# MAIN.net
KiCad netlist of a schematic drawn in Altium Designer
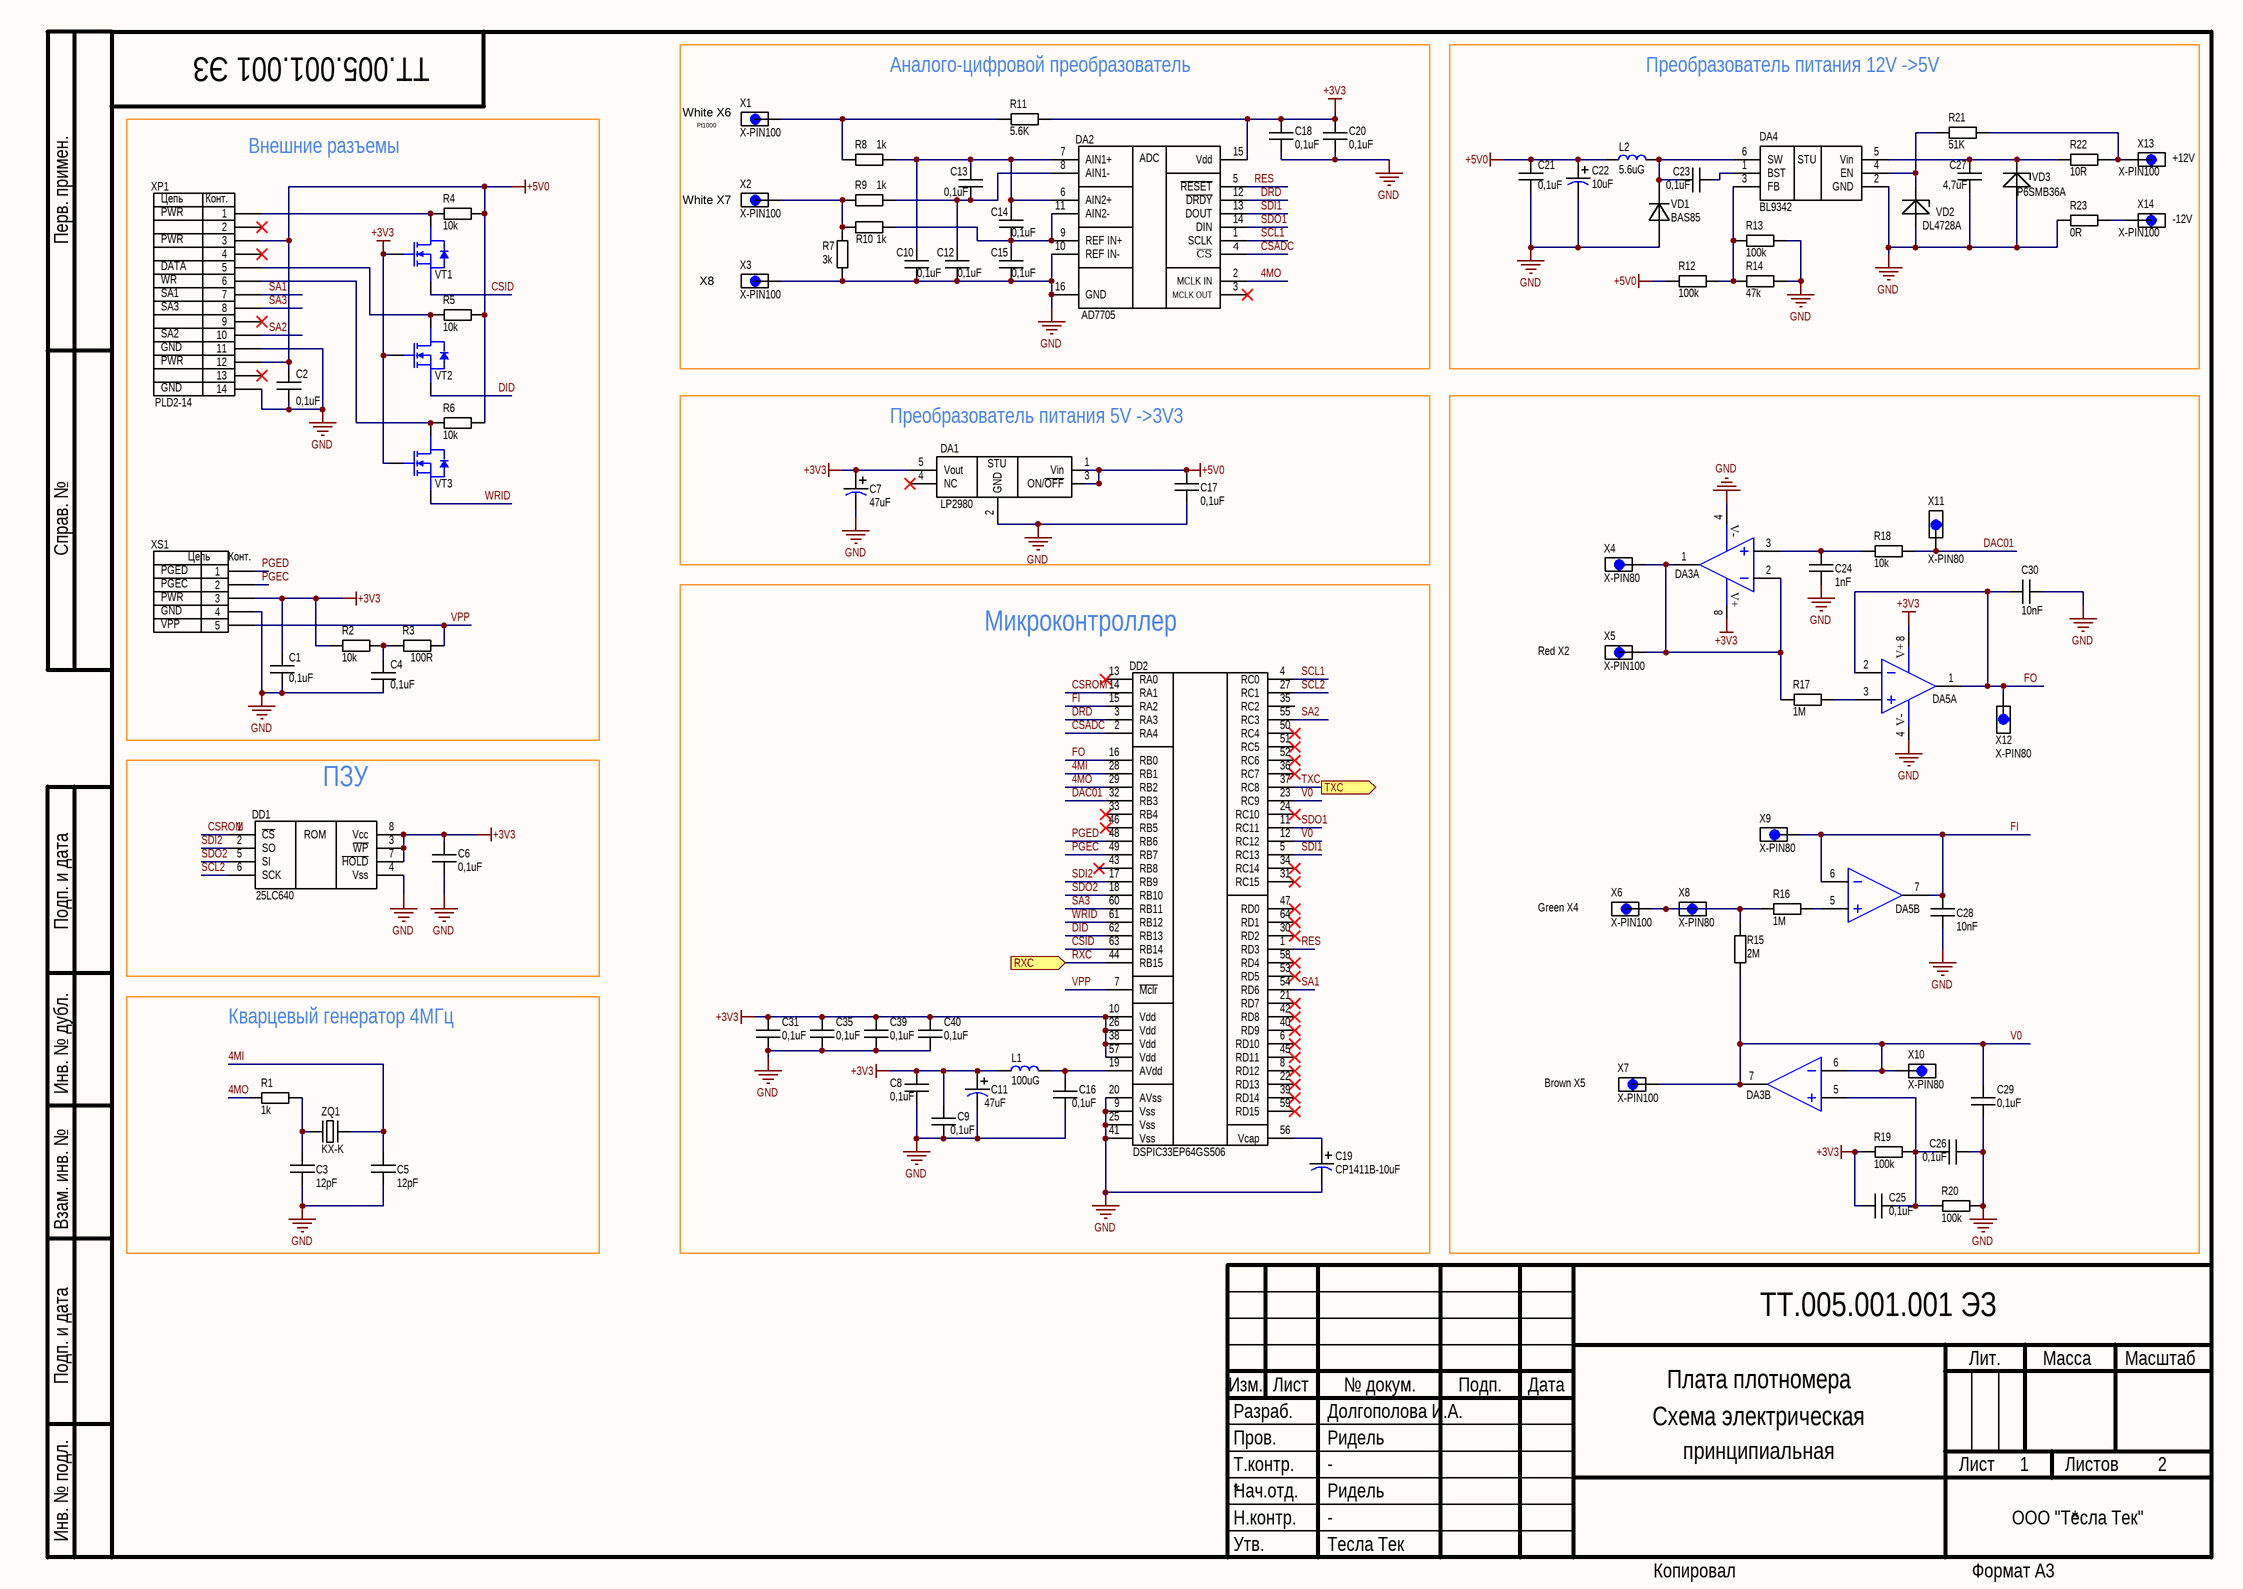
[diagram p0: MAIN.SCHDOC]

(export (version "E")
  (design (tool "Eeschema 10.0.6"))
  (components
    (comp (ref "C1")
      (value "0,1uF")
      (footprint "0805C")
      (description "C0805 0,1uF")
      (fields
        (field (name "PART NUMBER") "SMD CAP CER 0.1uF ±10% 25V X7R 0805")
        (field (name "ADDED_BY") "ridel_av@teslatec.ru")
      )
      (libsource (lib "81801_1") (part "C0805-0,1uF"))
    )
    (comp (ref "C2")
      (value "0,1uF")
      (footprint "0805C")
      (description "C0805 0,1uF")
      (fields
        (field (name "PART NUMBER") "SMD CAP CER 0.1uF ±10% 25V X7R 0805")
        (field (name "ADDED_BY") "ridel_av@teslatec.ru")
      )
      (libsource (lib "81801_1") (part "C0805-0,1uF"))
    )
    (comp (ref "C3")
      (value "12pF")
      (footprint "0805C")
      (description "C0805 12pF")
      (fields
        (field (name "PART NUMBER") "SMD CAP CER 12pF ±10% 10V X7R 0805")
        (field (name "ADDED_BY") "ridel_av@teslatec.ru")
      )
      (libsource (lib "81801_1") (part "C0805-12pF"))
    )
    (comp (ref "C4")
      (value "0,1uF")
      (footprint "0805C")
      (description "C0805 0,1uF")
      (fields
        (field (name "PART NUMBER") "SMD CAP CER 0.1uF ±10% 25V X7R 0805")
        (field (name "ADDED_BY") "ridel_av@teslatec.ru")
      )
      (libsource (lib "81801_1") (part "C0805-0,1uF"))
    )
    (comp (ref "C5")
      (value "12pF")
      (footprint "0805C")
      (description "C0805 12pF")
      (fields
        (field (name "PART NUMBER") "SMD CAP CER 12pF ±10% 10V X7R 0805")
        (field (name "ADDED_BY") "ridel_av@teslatec.ru")
      )
      (libsource (lib "81801_1") (part "C0805-12pF"))
    )
    (comp (ref "C6")
      (value "0,1uF")
      (footprint "0805C")
      (description "C0805 0,1uF")
      (fields
        (field (name "PART NUMBER") "SMD CAP CER 0.1uF ±10% 25V X7R 0805")
        (field (name "ADDED_BY") "ridel_av@teslatec.ru")
      )
      (libsource (lib "81801_1") (part "C0805-0,1uF"))
    )
    (comp (ref "C7")
      (value "47uF")
      (footprint "B1411_3528")
      (description "CP1411B 47UF 6V3")
      (fields
        (field (name "PART NUMBER") "SMD CAP TANTAL 47uF ±10% 6V3 1411B")
        (field (name "ADDED_BY") "ridel_av@teslatec.ru")
      )
      (libsource (lib "81801_1") (part "CP1411B-47UF"))
    )
    (comp (ref "C8")
      (value "0,1uF")
      (footprint "0805C")
      (description "C0805 0,1uF")
      (fields
        (field (name "PART NUMBER") "SMD CAP CER 0.1uF ±10% 25V X7R 0805")
        (field (name "ADDED_BY") "ridel_av@teslatec.ru")
      )
      (libsource (lib "81801_1") (part "C0805-0,1uF"))
    )
    (comp (ref "C9")
      (value "0,1uF")
      (footprint "0805C")
      (description "C0805 0,1uF")
      (fields
        (field (name "PART NUMBER") "SMD CAP CER 0.1uF ±10% 25V X7R 0805")
        (field (name "ADDED_BY") "ridel_av@teslatec.ru")
      )
      (libsource (lib "81801_1") (part "C0805-0,1uF"))
    )
    (comp (ref "C10")
      (value "0,1uF")
      (footprint "0805C")
      (description "C0805 0,1uF")
      (fields
        (field (name "PART NUMBER") "SMD CAP CER 0.1uF ±10% 25V X7R 0805")
        (field (name "ADDED_BY") "ridel_av@teslatec.ru")
      )
      (libsource (lib "81801_1") (part "C0805-0,1uF"))
    )
    (comp (ref "C11")
      (value "47uF")
      (footprint "B1411_3528")
      (description "CP1411B 47UF 6V3")
      (fields
        (field (name "PART NUMBER") "SMD CAP TANTAL 47uF ±10% 6V3 1411B")
        (field (name "ADDED_BY") "ridel_av@teslatec.ru")
      )
      (libsource (lib "81801_1") (part "CP1411B-47UF"))
    )
    (comp (ref "C12")
      (value "0,1uF")
      (footprint "0805C")
      (description "C0805 0,1uF")
      (fields
        (field (name "PART NUMBER") "SMD CAP CER 0.1uF ±10% 25V X7R 0805")
        (field (name "ADDED_BY") "ridel_av@teslatec.ru")
      )
      (libsource (lib "81801_1") (part "C0805-0,1uF"))
    )
    (comp (ref "C13")
      (value "0,1uF")
      (footprint "0805C")
      (description "C0805 0,1uF")
      (fields
        (field (name "PART NUMBER") "SMD CAP CER 0.1uF ±10% 25V X7R 0805")
        (field (name "ADDED_BY") "ridel_av@teslatec.ru")
      )
      (libsource (lib "81801_1") (part "C0805-0,1uF"))
    )
    (comp (ref "C14")
      (value "0,1uF")
      (footprint "0805C")
      (description "C0805 0,1uF")
      (fields
        (field (name "PART NUMBER") "SMD CAP CER 0.1uF ±10% 25V X7R 0805")
        (field (name "ADDED_BY") "ridel_av@teslatec.ru")
      )
      (libsource (lib "81801_1") (part "C0805-0,1uF"))
    )
    (comp (ref "C15")
      (value "0,1uF")
      (footprint "0805C")
      (description "C0805 0,1uF")
      (fields
        (field (name "PART NUMBER") "SMD CAP CER 0.1uF ±10% 25V X7R 0805")
        (field (name "ADDED_BY") "ridel_av@teslatec.ru")
      )
      (libsource (lib "81801_1") (part "C0805-0,1uF"))
    )
    (comp (ref "C16")
      (value "0,1uF")
      (footprint "0805C")
      (description "C0805 0,1uF")
      (fields
        (field (name "PART NUMBER") "SMD CAP CER 0.1uF ±10% 25V X7R 0805")
        (field (name "ADDED_BY") "ridel_av@teslatec.ru")
      )
      (libsource (lib "81801_1") (part "C0805-0,1uF"))
    )
    (comp (ref "C17")
      (value "0,1uF")
      (footprint "0805C")
      (description "C0805 0,1uF")
      (fields
        (field (name "PART NUMBER") "SMD CAP CER 0.1uF ±10% 25V X7R 0805")
        (field (name "ADDED_BY") "ridel_av@teslatec.ru")
      )
      (libsource (lib "81801_1") (part "C0805-0,1uF"))
    )
    (comp (ref "C18")
      (value "0,1uF")
      (footprint "0805C")
      (description "C0805 0,1uF")
      (fields
        (field (name "PART NUMBER") "SMD CAP CER 0.1uF ±10% 25V X7R 0805")
        (field (name "ADDED_BY") "ridel_av@teslatec.ru")
      )
      (libsource (lib "81801_1") (part "C0805-0,1uF"))
    )
    (comp (ref "C19")
      (value "CP1411B-10uF")
      (footprint "B1411_3528")
      (description "CP1411B 10uF 6V3")
      (fields
        (field (name "PART NUMBER") "SMD CAP TANTAL 10uF ±10% 6V3 1411B")
        (field (name "ADDED_BY") "ridel_av@teslatec.ru")
      )
      (libsource (lib "81801_1") (part "CP1411B-10uF"))
    )
    (comp (ref "C20")
      (value "0,1uF")
      (footprint "0805C")
      (description "C0805 0,1uF")
      (fields
        (field (name "PART NUMBER") "SMD CAP CER 0.1uF ±10% 25V X7R 0805")
        (field (name "ADDED_BY") "ridel_av@teslatec.ru")
      )
      (libsource (lib "81801_1") (part "C0805-0,1uF"))
    )
    (comp (ref "C21")
      (value "0,1uF")
      (footprint "0805C")
      (description "C0805 0,1uF")
      (fields
        (field (name "PART NUMBER") "SMD CAP CER 0.1uF ±10% 25V X7R 0805")
        (field (name "ADDED_BY") "ridel_av@teslatec.ru")
      )
      (libsource (lib "81801_1") (part "C0805-0,1uF"))
    )
    (comp (ref "C22")
      (value "10uF")
      (footprint "B1411_3528")
      (description "CP1411B 10uF 10V")
      (fields
        (field (name "PART NUMBER") "SMD CAP TANTAL 10uF ±10% 10V 1411B")
        (field (name "ADDED_BY") "ridel_av@teslatec.ru")
      )
      (libsource (lib "81801_1") (part "CP1411B-10uF-10V"))
    )
    (comp (ref "C23")
      (value "0,1uF")
      (footprint "0805C")
      (description "C0805 0,1uF")
      (fields
        (field (name "PART NUMBER") "SMD CAP CER 0.1uF ±10% 25V X7R 0805")
        (field (name "ADDED_BY") "ridel_av@teslatec.ru")
      )
      (libsource (lib "81801_1") (part "C0805-0,1uF"))
    )
    (comp (ref "C24")
      (value "1nF")
      (footprint "0805C")
      (description "C0805 1nF")
      (fields
        (field (name "PART NUMBER") "SMD CAP CER 1nF ±10% 50V X7R 0805")
        (field (name "ADDED_BY") "ridel_av@teslatec.ru")
      )
      (libsource (lib "81801_1") (part "C0805-1nF"))
    )
    (comp (ref "C25")
      (value "0,1uF")
      (footprint "0805C")
      (description "C0805 0,1uF")
      (fields
        (field (name "PART NUMBER") "SMD CAP CER 0.1uF ±10% 25V X7R 0805")
        (field (name "ADDED_BY") "ridel_av@teslatec.ru")
      )
      (libsource (lib "81801_1") (part "C0805-0,1uF"))
    )
    (comp (ref "C26")
      (value "0,1uF")
      (footprint "0805C")
      (description "C0805 0,1uF")
      (fields
        (field (name "PART NUMBER") "SMD CAP CER 0.1uF ±10% 25V X7R 0805")
        (field (name "ADDED_BY") "ridel_av@teslatec.ru")
      )
      (libsource (lib "81801_1") (part "C0805-0,1uF"))
    )
    (comp (ref "C27")
      (value "4,7uF")
      (footprint "0805C")
      (description "C0805 4,7uF 50V")
      (fields
        (field (name "PART NUMBER") "SMD CAP CER 4.7uF ±10% 50V X7R 0805")
        (field (name "ADDED_BY") "ridel_av@teslatec.ru")
      )
      (libsource (lib "81801_1") (part "C0805-4,7uF"))
    )
    (comp (ref "C28")
      (value "10nF")
      (footprint "0805C")
      (description "C0805 10nF")
      (fields
        (field (name "PART NUMBER") "SMD CAP CER 10nF ±10% 50V X7R 0805")
        (field (name "ADDED_BY") "ridel_av@teslatec.ru")
      )
      (libsource (lib "81801_1") (part "C0805-10nF"))
    )
    (comp (ref "C29")
      (value "0,1uF")
      (footprint "0805C")
      (description "C0805 0,1uF")
      (fields
        (field (name "PART NUMBER") "SMD CAP CER 0.1uF ±10% 25V X7R 0805")
        (field (name "ADDED_BY") "ridel_av@teslatec.ru")
      )
      (libsource (lib "81801_1") (part "C0805-0,1uF"))
    )
    (comp (ref "C30")
      (value "10nF")
      (footprint "0805C")
      (description "C0805 10nF")
      (fields
        (field (name "PART NUMBER") "SMD CAP CER 10nF ±10% 50V X7R 0805")
        (field (name "ADDED_BY") "ridel_av@teslatec.ru")
      )
      (libsource (lib "81801_1") (part "C0805-10nF"))
    )
    (comp (ref "C31")
      (value "0,1uF")
      (footprint "0805C")
      (description "C0805 0,1uF")
      (fields
        (field (name "PART NUMBER") "SMD CAP CER 0.1uF ±10% 25V X7R 0805")
        (field (name "ADDED_BY") "ridel_av@teslatec.ru")
      )
      (libsource (lib "81801_1") (part "C0805-0,1uF"))
    )
    (comp (ref "C35")
      (value "0,1uF")
      (footprint "0805C")
      (description "C0805 0,1uF")
      (fields
        (field (name "PART NUMBER") "SMD CAP CER 0.1uF ±10% 25V X7R 0805")
        (field (name "ADDED_BY") "ridel_av@teslatec.ru")
      )
      (libsource (lib "81801_1") (part "C0805-0,1uF"))
    )
    (comp (ref "C39")
      (value "0,1uF")
      (footprint "0805C")
      (description "C0805 0,1uF")
      (fields
        (field (name "PART NUMBER") "SMD CAP CER 0.1uF ±10% 25V X7R 0805")
        (field (name "ADDED_BY") "ridel_av@teslatec.ru")
      )
      (libsource (lib "81801_1") (part "C0805-0,1uF"))
    )
    (comp (ref "C40")
      (value "0,1uF")
      (footprint "0805C")
      (description "C0805 0,1uF")
      (fields
        (field (name "PART NUMBER") "SMD CAP CER 0.1uF ±10% 25V X7R 0805")
        (field (name "ADDED_BY") "ridel_av@teslatec.ru")
      )
      (libsource (lib "81801_1") (part "C0805-0,1uF"))
    )
    (comp (ref "DA1")
      (value "LP2980")
      (footprint "SOT23-5")
      (description "DA-STU-LP2980, 3.3V, 50mA")
      (fields
        (field (name "PART NUMBER") "LP2980IM5X-3.3/NOPB")
        (field (name "ADDED_BY") "ridel_av@teslatec.ru")
      )
      (libsource (lib "81801_1") (part "DA-STU-LP2980"))
    )
    (comp (ref "DA2")
      (value "AD7705")
      (footprint "SOIC-16")
      (description "DA-ADC-AD7705")
      (fields (field (name "PART NUMBER") "AD7705BR") (field (name "ADDED_BY") "ridel_av@teslatec.ru"))
      (libsource (lib "81801_1") (part "DA-ADC-AD7705SO"))
    )
    (comp (ref "DA3")
      (value "TP6002-SR")
      (footprint "SOIC-8")
      (description "100 mA Output Single-Supply Amplifier")
      (fields (field (name "ADDED_BY") "ridel_av@teslatec.ru"))
      (libsource (lib "81801_1") (part "TP6002-SR"))
    )
    (comp (ref "DA4")
      (value "BL9342")
      (footprint "SOT23-6")
      (description "STU-BL9342, 40V, 600mA")
      (fields (field (name "ADDED_BY") "ridel_av@teslatec.ru"))
      (libsource (lib "81801_1") (part "BL9342"))
    )
    (comp (ref "DA5")
      (value "TP6002-SR")
      (footprint "SOIC-8")
      (description "100 mA Output Single-Supply Amplifier")
      (fields (field (name "ADDED_BY") "ridel_av@teslatec.ru"))
      (libsource (lib "81801_1") (part "TP6002-SR"))
    )
    (comp (ref "DD1")
      (value "25LC640")
      (footprint "SOIC-8")
      (description "25LC640-E/SN, EEPROM, 64Kbit, 2MHz, SPI")
      (fields (field (name "PART NUMBER") "25LC640-E/SN") (field (name "ADDED_BY") "ridel_av@teslatec.ru"))
      (libsource (lib "81801_1") (part "25LC640"))
    )
    (comp (ref "DD2")
      (value "DSPIC33EP64GS506")
      (footprint "TQFP-64")
      (description "DD-CPU-DSPIC33EP64GS506")
      (fields (field (name "ADDED_BY") "ridel_av@teslatec.ru"))
      (libsource (lib "81801_1") (part "DD-CPU-DSPIC33EPXXGS506"))
    )
    (comp (ref "L1")
      (value "100uG")
      (footprint "L1206")
      (description "LQH31CN101K03L, 100 uG, 1206, 10%")
      (fields (field (name "PART NUMBER") "LQH31CN101K03L") (field (name "ADDED_BY") "ridel_av@teslatec.ru"))
      (libsource (lib "81801_1") (part "L1206-100uG"))
    )
    (comp (ref "L2")
      (value "5.6uG")
      (footprint "L1210")
      (description "LQH32MN5R6K23L, 5.6uG, 1210, 10%")
      (fields (field (name "PART NUMBER") "LQH32MN5R6K23L") (field (name "ADDED_BY") "ridel_av@teslatec.ru"))
      (libsource (lib "81801_1") (part "L1210-5.6uG"))
    )
    (comp (ref "R1")
      (value "1k")
      (footprint "R1206")
      (description "R1206 SMD 1k OHM 1% ±100ppm/°C")
      (fields
        (field (name "PART NUMBER") "SMD RES 1k OHM 1% ±100ppm/°C 1206")
        (field (name "ADDED_BY") "ridel_av@teslatec.ru")
      )
      (libsource (lib "81801_1") (part "R1206-1k"))
    )
    (comp (ref "R2")
      (value "10k")
      (footprint "R0805")
      (description "R0805 SMD 10k OHM 1% ±100ppm/°C")
      (fields
        (field (name "PART NUMBER") "SMD RES 10k OHM 1% ±100ppm/°C 0805")
        (field (name "ADDED_BY") "ridel_av@teslatec.ru")
      )
      (libsource (lib "81801_1") (part "R0805-10k"))
    )
    (comp (ref "R3")
      (value "100R")
      (footprint "R1206")
      (description "R1206 100 OHM 1% ±100ppm/°C")
      (fields
        (field (name "PART NUMBER") "SMD RES 100 OHM 1% ±100ppm/°C 1206")
        (field (name "ADDED_BY") "ridel_av@teslatec.ru")
      )
      (libsource (lib "81801_1") (part "R1206-100R"))
    )
    (comp (ref "R4")
      (value "10k")
      (footprint "R0805")
      (description "R0805 SMD 10k OHM 1% ±100ppm/°C")
      (fields
        (field (name "PART NUMBER") "SMD RES 10k OHM 1% ±100ppm/°C 0805")
        (field (name "ADDED_BY") "ridel_av@teslatec.ru")
      )
      (libsource (lib "81801_1") (part "R0805-10k"))
    )
    (comp (ref "R5")
      (value "10k")
      (footprint "R0805")
      (description "R0805 SMD 10k OHM 1% ±100ppm/°C")
      (fields
        (field (name "PART NUMBER") "SMD RES 10k OHM 1% ±100ppm/°C 0805")
        (field (name "ADDED_BY") "ridel_av@teslatec.ru")
      )
      (libsource (lib "81801_1") (part "R0805-10k"))
    )
    (comp (ref "R6")
      (value "10k")
      (footprint "R0805")
      (description "R0805 SMD 10k OHM 1% ±100ppm/°C")
      (fields
        (field (name "PART NUMBER") "SMD RES 10k OHM 1% ±100ppm/°C 0805")
        (field (name "ADDED_BY") "ridel_av@teslatec.ru")
      )
      (libsource (lib "81801_1") (part "R0805-10k"))
    )
    (comp (ref "R7")
      (value "3k")
      (footprint "R1206")
      (description "R1206 SMD 3k OHM 1% ±100ppm/°C")
      (fields
        (field (name "PART NUMBER") "SMD RES 1k OHM 1% ±100ppm/°C 1206")
        (field (name "ADDED_BY") "ridel_av@teslatec.ru")
      )
      (libsource (lib "81801_1") (part "R1206-3k"))
    )
    (comp (ref "R8")
      (value "1k")
      (footprint "R1206")
      (description "R1206 SMD 1k OHM 1% ±100ppm/°C")
      (fields
        (field (name "PART NUMBER") "SMD RES 1k OHM 1% ±100ppm/°C 1206")
        (field (name "ADDED_BY") "ridel_av@teslatec.ru")
      )
      (libsource (lib "81801_1") (part "R1206-1k"))
    )
    (comp (ref "R9")
      (value "1k")
      (footprint "R1206")
      (description "R1206 SMD 1k OHM 1% ±100ppm/°C")
      (fields
        (field (name "PART NUMBER") "SMD RES 1k OHM 1% ±100ppm/°C 1206")
        (field (name "ADDED_BY") "ridel_av@teslatec.ru")
      )
      (libsource (lib "81801_1") (part "R1206-1k"))
    )
    (comp (ref "R10")
      (value "1k")
      (footprint "R1206")
      (description "R1206 SMD 1k OHM 1% ±100ppm/°C")
      (fields
        (field (name "PART NUMBER") "SMD RES 1k OHM 1% ±100ppm/°C 1206")
        (field (name "ADDED_BY") "ridel_av@teslatec.ru")
      )
      (libsource (lib "81801_1") (part "R1206-1k"))
    )
    (comp (ref "R11")
      (value "5.6K")
      (footprint "R1206")
      (description "R1206 5.6k OHM 1% ±100ppm/°C")
      (fields
        (field (name "PART NUMBER") "SMD RES 5.6k OHM 1% ±100ppm/°C 1206")
        (field (name "ADDED_BY") "ridel_av@teslatec.ru")
      )
      (libsource (lib "81801_1") (part "R1206-5.6K"))
    )
    (comp (ref "R12")
      (value "100k")
      (footprint "R1206")
      (description "R1206 100k OHM 1% ±100ppm/°C")
      (fields
        (field (name "PART NUMBER") "SMD RES 100k OHM 1% ±100ppm/°C 1206")
        (field (name "ADDED_BY") "ridel_av@teslatec.ru")
      )
      (libsource (lib "81801_1") (part "R1206-100k"))
    )
    (comp (ref "R13")
      (value "100k")
      (footprint "R1206")
      (description "R1206 100k OHM 1% ±100ppm/°C")
      (fields
        (field (name "PART NUMBER") "SMD RES 100k OHM 1% ±100ppm/°C 1206")
        (field (name "ADDED_BY") "ridel_av@teslatec.ru")
      )
      (libsource (lib "81801_1") (part "R1206-100k"))
    )
    (comp (ref "R14")
      (value "47k")
      (footprint "R1206")
      (description "R1206 47k OHM 1% ±100ppm/°C")
      (fields
        (field (name "PART NUMBER") "SMD RES 47k OHM 1% ±100ppm/°C 1206")
        (field (name "ADDED_BY") "ridel_av@teslatec.ru")
      )
      (libsource (lib "81801_1") (part "R1206-47k"))
    )
    (comp (ref "R15")
      (value "2M")
      (footprint "R1206")
      (description "R1206 2M OHM 1% ±100ppm/°C")
      (fields
        (field (name "PART NUMBER") "SMD RES 2M OHM 1% ±100ppm/°C 1206")
        (field (name "ADDED_BY") "ridel_av@teslatec.ru")
      )
      (libsource (lib "81801_1") (part "R1206-2M"))
    )
    (comp (ref "R16")
      (value "1M")
      (footprint "R1206")
      (description "R1206 1M OHM 1% ±100ppm/°C")
      (fields
        (field (name "PART NUMBER") "SMD RES 1M OHM 1% ±100ppm/°C 1206")
        (field (name "ADDED_BY") "ridel_av@teslatec.ru")
      )
      (libsource (lib "81801_1") (part "R1206-1M"))
    )
    (comp (ref "R17")
      (value "1M")
      (footprint "R1206")
      (description "R1206 1M OHM 1% ±100ppm/°C")
      (fields
        (field (name "PART NUMBER") "SMD RES 1M OHM 1% ±100ppm/°C 1206")
        (field (name "ADDED_BY") "ridel_av@teslatec.ru")
      )
      (libsource (lib "81801_1") (part "R1206-1M"))
    )
    (comp (ref "R18")
      (value "10k")
      (footprint "R0805")
      (description "R0805 SMD 10k OHM 1% ±100ppm/°C")
      (fields
        (field (name "PART NUMBER") "SMD RES 10k OHM 1% ±100ppm/°C 0805")
        (field (name "ADDED_BY") "ridel_av@teslatec.ru")
      )
      (libsource (lib "81801_1") (part "R0805-10k"))
    )
    (comp (ref "R19")
      (value "100k")
      (footprint "R1206")
      (description "R1206 100k OHM 1% ±100ppm/°C")
      (fields
        (field (name "PART NUMBER") "SMD RES 100k OHM 1% ±100ppm/°C 1206")
        (field (name "ADDED_BY") "ridel_av@teslatec.ru")
      )
      (libsource (lib "81801_1") (part "R1206-100k"))
    )
    (comp (ref "R20")
      (value "100k")
      (footprint "R1206")
      (description "R1206 100k OHM 1% ±100ppm/°C")
      (fields
        (field (name "PART NUMBER") "SMD RES 100k OHM 1% ±100ppm/°C 1206")
        (field (name "ADDED_BY") "ridel_av@teslatec.ru")
      )
      (libsource (lib "81801_1") (part "R1206-100k"))
    )
    (comp (ref "R21")
      (value "51K")
      (footprint "R1206")
      (description "R1206 51K OHM 1% ±100ppm/°C")
      (fields
        (field (name "PART NUMBER") "SMD RES 51K OHM 1% ±100ppm/°C 1206")
        (field (name "ADDED_BY") "ridel_av@teslatec.ru")
      )
      (libsource (lib "81801_1") (part "R1206-51K"))
    )
    (comp (ref "R22")
      (value "10R")
      (footprint "R1206")
      (description "R1206 10 OHM 1% ±100ppm/°C")
      (fields
        (field (name "PART NUMBER") "SMD RES 10 OHM 1% ±100ppm/°C 1206")
        (field (name "ADDED_BY") "ridel_av@teslatec.ru")
      )
      (libsource (lib "81801_1") (part "R1206-10R"))
    )
    (comp (ref "R23")
      (value "0R")
      (footprint "R1206")
      (description "R1206-0R")
      (fields
        (field (name "PART NUMBER") "SMD RES 0 OHM 1% ±100ppm/°C 1206")
        (field (name "ADDED_BY") "ridel_av@teslatec.ru")
      )
      (libsource (lib "81801_1") (part "R1206-0R"))
    )
    (comp (ref "VD1")
      (value "BAS85")
      (footprint "SOD-80 MiniMELF")
      (description "BAS85 30В 0.2А")
      (fields (field (name "ADDED_BY") "ridel_av@teslatec.ru"))
      (libsource (lib "81801_1") (part "BAS85"))
    )
    (comp (ref "VD2")
      (value "DL4728A")
      (footprint "DO-213AB")
      (description "DL4728A, 3V3")
      (fields (field (name "ADDED_BY") "ridel_av@teslatec.ru"))
      (libsource (lib "81801_1") (part "DL4728A"))
    )
    (comp (ref "VD3")
      (value "P6SMB36A")
      (footprint "SMB(DO-214AA )")
      (description "P6SMB36A, 49.9V")
      (fields (field (name "ADDED_BY") "ridel_av@teslatec.ru"))
      (libsource (lib "81801_1") (part "P6SMB36A"))
    )
    (comp (ref "VT1")
      (value "VT-MOSFET-N-SOT23")
      (footprint "SOT-23-3")
      (description "2N7002, MOSFET-N, 60V, 115mA, SOT-23-3")
      (fields (field (name "PART NUMBER") "2N7002") (field (name "ADDED_BY") "ridel_av@teslatec.ru"))
      (libsource (lib "81801_1") (part "2N7002"))
    )
    (comp (ref "VT2")
      (value "VT-MOSFET-N-SOT23")
      (footprint "SOT-23-3")
      (description "2N7002, MOSFET-N, 60V, 115mA, SOT-23-3")
      (fields (field (name "PART NUMBER") "2N7002") (field (name "ADDED_BY") "ridel_av@teslatec.ru"))
      (libsource (lib "81801_1") (part "2N7002"))
    )
    (comp (ref "VT3")
      (value "VT-MOSFET-N-SOT23")
      (footprint "SOT-23-3")
      (description "2N7002, MOSFET-N, 60V, 115mA, SOT-23-3")
      (fields (field (name "PART NUMBER") "2N7002") (field (name "ADDED_BY") "ridel_av@teslatec.ru"))
      (libsource (lib "81801_1") (part "2N7002"))
    )
    (comp (ref "X1")
      (value "X-PIN100")
      (footprint "Xpin100")
      (fields (field (name "ADDED_BY") "ridel_av@teslatec.ru"))
      (libsource (lib "81801_1") (part "X-PIN100"))
    )
    (comp (ref "X2")
      (value "X-PIN100")
      (footprint "Xpin100")
      (fields (field (name "ADDED_BY") "ridel_av@teslatec.ru"))
      (libsource (lib "81801_1") (part "X-PIN100"))
    )
    (comp (ref "X3")
      (value "X-PIN100")
      (footprint "Xpin100")
      (fields (field (name "ADDED_BY") "ridel_av@teslatec.ru"))
      (libsource (lib "81801_1") (part "X-PIN100"))
    )
    (comp (ref "X4")
      (value "X-PIN80")
      (footprint "Xpin80")
      (fields (field (name "ADDED_BY") "ridel_av@teslatec.ru"))
      (libsource (lib "81801_1") (part "X-PIN80"))
    )
    (comp (ref "X5")
      (value "X-PIN100")
      (footprint "Xpin100")
      (fields (field (name "ADDED_BY") "ridel_av@teslatec.ru"))
      (libsource (lib "81801_1") (part "X-PIN100"))
    )
    (comp (ref "X6")
      (value "X-PIN100")
      (footprint "Xpin100")
      (fields (field (name "ADDED_BY") "ridel_av@teslatec.ru"))
      (libsource (lib "81801_1") (part "X-PIN100"))
    )
    (comp (ref "X7")
      (value "X-PIN100")
      (footprint "Xpin100")
      (fields (field (name "ADDED_BY") "ridel_av@teslatec.ru"))
      (libsource (lib "81801_1") (part "X-PIN100"))
    )
    (comp (ref "X8")
      (value "X-PIN80")
      (footprint "Xpin80")
      (fields (field (name "ADDED_BY") "ridel_av@teslatec.ru"))
      (libsource (lib "81801_1") (part "X-PIN80"))
    )
    (comp (ref "X9")
      (value "X-PIN80")
      (footprint "Xpin80")
      (fields (field (name "ADDED_BY") "ridel_av@teslatec.ru"))
      (libsource (lib "81801_1") (part "X-PIN80"))
    )
    (comp (ref "X10")
      (value "X-PIN80")
      (footprint "Xpin80")
      (fields (field (name "ADDED_BY") "ridel_av@teslatec.ru"))
      (libsource (lib "81801_1") (part "X-PIN80"))
    )
    (comp (ref "X11")
      (value "X-PIN80")
      (footprint "Xpin80")
      (fields (field (name "ADDED_BY") "ridel_av@teslatec.ru"))
      (libsource (lib "81801_1") (part "X-PIN80"))
    )
    (comp (ref "X12")
      (value "X-PIN80")
      (footprint "Xpin80")
      (fields (field (name "ADDED_BY") "ridel_av@teslatec.ru"))
      (libsource (lib "81801_1") (part "X-PIN80"))
    )
    (comp (ref "X13")
      (value "X-PIN100")
      (footprint "Xpin100")
      (fields (field (name "ADDED_BY") "ridel_av@teslatec.ru"))
      (libsource (lib "81801_1") (part "X-PIN100"))
    )
    (comp (ref "X14")
      (value "X-PIN100")
      (footprint "Xpin100")
      (fields (field (name "ADDED_BY") "ridel_av@teslatec.ru"))
      (libsource (lib "81801_1") (part "X-PIN100"))
    )
    (comp (ref "XP1")
      (value "PLD2-14")
      (footprint "PLD-14- 2.0mm")
      (fields
        (field (name "PART NUMBER") "DS1025-05-2X7P8BV1-B")
        (field (name "ADDED_BY") "ridel_av@teslatec.ru")
      )
      (libsource (lib "81801_1") (part "PLD2-14"))
    )
    (comp (ref "XS1")
      (value "PBS2-5")
      (footprint "PBS-5")
      (fields (field (name "PART NUMBER") "C6801-05ASGL00R") (field (name "ADDED_BY") "ridel_av@teslatec.ru"))
      (libsource (lib "81801_1") (part "PBS2-5"))
    )
    (comp (ref "ZQ1")
      (value "KX-K")
      (footprint "HC¦49US")
      (description "KX-K 4MHz HC/49US")
      (fields
        (field (name "PART NUMBER") "ABLS-4.000MHZ-K4T")
        (field (name "ADDED_BY") "ridel_av@teslatec.ru")
      )
      (libsource (lib "81801_1") (part "ABLS-4.000MHZ-K4T"))
    )
  )
  (nets
    (net (code "1") (name "+3V3") (class "Default")
      (node (ref "C1") (pin "1") (pinfunction "1_1") (pintype "passive"))
      (node (ref "C11") (pin "1") (pinfunction "1_1") (pintype "passive"))
      (node (ref "C18") (pin "2") (pinfunction "2_2") (pintype "passive"))
      (node (ref "C20") (pin "1") (pinfunction "1_1") (pintype "passive"))
      (node (ref "C25") (pin "1") (pinfunction "1_1") (pintype "passive"))
      (node (ref "C31") (pin "1") (pinfunction "1_1") (pintype "passive"))
      (node (ref "C35") (pin "1") (pinfunction "1_1") (pintype "passive"))
      (node (ref "C39") (pin "1") (pinfunction "1_1") (pintype "passive"))
      (node (ref "C40") (pin "1") (pinfunction "1_1") (pintype "passive"))
      (node (ref "C6") (pin "2") (pinfunction "2_2") (pintype "passive"))
      (node (ref "C7") (pin "1") (pinfunction "1_1") (pintype "passive"))
      (node (ref "C8") (pin "1") (pinfunction "1_1") (pintype "passive"))
      (node (ref "C9") (pin "1") (pinfunction "1_1") (pintype "passive"))
      (node (ref "DA1") (pin "5") (pinfunction "Vout_5") (pintype "passive"))
      (node (ref "DA2") (pin "15") (pinfunction "Vdd_15") (pintype "power_in"))
      (node (ref "DA3") (pin "8") (pinfunction "8_8") (pintype "passive"))
      (node (ref "DA5") (pin "8") (pinfunction "8_8") (pintype "passive"))
      (node (ref "DD1") (pin "3") (pinfunction "~{WP}_3") (pintype "passive"))
      (node (ref "DD1") (pin "7") (pinfunction "~{HOLD}_7") (pintype "passive"))
      (node (ref "DD1") (pin "8") (pinfunction "Vcc_8") (pintype "passive"))
      (node (ref "DD2") (pin "10") (pinfunction "Vdd_10") (pintype "passive"))
      (node (ref "DD2") (pin "26") (pinfunction "Vdd_26") (pintype "passive"))
      (node (ref "DD2") (pin "38") (pinfunction "Vdd_38") (pintype "passive"))
      (node (ref "DD2") (pin "57") (pinfunction "Vdd_57") (pintype "passive"))
      (node (ref "L1") (pin "1") (pinfunction "1_1") (pintype "passive"))
      (node (ref "R11") (pin "2") (pinfunction "2_2") (pintype "passive"))
      (node (ref "R19") (pin "1") (pinfunction "1_1") (pintype "passive"))
      (node (ref "R2") (pin "1") (pinfunction "1_1") (pintype "passive"))
      (node (ref "VT1") (pin "1") (pinfunction "1_1") (pintype "passive"))
      (node (ref "VT2") (pin "1") (pinfunction "1_1") (pintype "passive"))
      (node (ref "VT3") (pin "1") (pinfunction "1_1") (pintype "passive"))
      (node (ref "XS1") (pin "3") (pinfunction "3_3") (pintype "passive"))
    )
    (net (code "2") (name "+5V0") (class "Default")
      (node (ref "C17") (pin "1") (pinfunction "1_1") (pintype "passive"))
      (node (ref "C2") (pin "1") (pinfunction "1_1") (pintype "passive"))
      (node (ref "C21") (pin "1") (pinfunction "1_1") (pintype "passive"))
      (node (ref "C22") (pin "1") (pinfunction "1_1") (pintype "passive"))
      (node (ref "DA1") (pin "1") (pinfunction "Vin_1") (pintype "passive"))
      (node (ref "DA1") (pin "3") (pinfunction "ON/~{OFF}_3") (pintype "passive"))
      (node (ref "L2") (pin "1") (pinfunction "1_1") (pintype "passive"))
      (node (ref "R12") (pin "1") (pinfunction "1_1") (pintype "passive"))
      (node (ref "R4") (pin "2") (pinfunction "2_2") (pintype "passive"))
      (node (ref "R5") (pin "2") (pinfunction "2_2") (pintype "passive"))
      (node (ref "R6") (pin "2") (pinfunction "2_2") (pintype "passive"))
      (node (ref "XP1") (pin "12") (pinfunction "12_12") (pintype "passive"))
      (node (ref "XP1") (pin "3") (pinfunction "3_3") (pintype "passive"))
    )
    (net (code "3") (name "/4MI") (class "Default")
      (node (ref "C5") (pin "1") (pinfunction "1_1") (pintype "passive"))
      (node (ref "DD2") (pin "28") (pinfunction "RB1_28") (pintype "passive"))
      (node (ref "ZQ1") (pin "2") (pinfunction "OSC2_2") (pintype "passive"))
    )
    (net (code "4") (name "/4MO") (class "Default")
      (node (ref "DA2") (pin "2") (pinfunction "MCLK_IN_2") (pintype "passive"))
      (node (ref "DD2") (pin "29") (pinfunction "RB2_29") (pintype "passive"))
      (node (ref "R1") (pin "1") (pinfunction "1_1") (pintype "passive"))
    )
    (net (code "5") (name "/CSADC") (class "Default")
      (node (ref "DA2") (pin "4") (pinfunction "~{CS}_4") (pintype "passive"))
      (node (ref "DD2") (pin "2") (pinfunction "RA4_2") (pintype "passive"))
    )
    (net (code "6") (name "/CSID") (class "Default")
      (node (ref "DD2") (pin "63") (pinfunction "RB14_63") (pintype "passive"))
      (node (ref "VT1") (pin "2") (pinfunction "2_2") (pintype "passive"))
    )
    (net (code "7") (name "/CSROM") (class "Default")
      (node (ref "DD1") (pin "1") (pinfunction "~{CS}_1") (pintype "passive"))
      (node (ref "DD2") (pin "14") (pinfunction "RA1_14") (pintype "passive"))
    )
    (net (code "8") (name "/DAC01") (class "Default")
      (node (ref "DD2") (pin "32") (pinfunction "RB3_32") (pintype "passive"))
      (node (ref "R18") (pin "2") (pinfunction "2_2") (pintype "passive"))
      (node (ref "X11") (pin "1") (pinfunction "Contact0_1") (pintype "passive"))
    )
    (net (code "9") (name "/DID") (class "Default")
      (node (ref "DD2") (pin "62") (pinfunction "RB13_62") (pintype "passive"))
      (node (ref "VT2") (pin "2") (pinfunction "2_2") (pintype "passive"))
    )
    (net (code "10") (name "/DRD") (class "Default")
      (node (ref "DA2") (pin "12") (pinfunction "~{DRDY}_12") (pintype "passive"))
      (node (ref "DD2") (pin "3") (pinfunction "RA3_3") (pintype "passive"))
    )
    (net (code "11") (name "/FI") (class "Default")
      (node (ref "C28") (pin "1") (pinfunction "1_1") (pintype "passive"))
      (node (ref "DA5") (pin "6") (pinfunction "6_6") (pintype "passive"))
      (node (ref "DA5") (pin "7") (pinfunction "7_7") (pintype "passive"))
      (node (ref "DD2") (pin "15") (pinfunction "RA2_15") (pintype "passive"))
      (node (ref "X9") (pin "1") (pinfunction "Contact0_1") (pintype "passive"))
    )
    (net (code "12") (name "/FO") (class "Default")
      (node (ref "C30") (pin "1") (pinfunction "1_1") (pintype "passive"))
      (node (ref "DA5") (pin "1") (pinfunction "1_1") (pintype "passive"))
      (node (ref "DA5") (pin "2") (pinfunction "2_2") (pintype "passive"))
      (node (ref "DD2") (pin "16") (pinfunction "RB0_16") (pintype "passive"))
      (node (ref "X12") (pin "1") (pinfunction "Contact0_1") (pintype "passive"))
    )
    (net (code "13") (name "/PGEC") (class "Default")
      (node (ref "DD2") (pin "49") (pinfunction "RB7_49") (pintype "passive"))
      (node (ref "XS1") (pin "2") (pinfunction "2_2") (pintype "passive"))
    )
    (net (code "14") (name "/PGED") (class "Default")
      (node (ref "DD2") (pin "48") (pinfunction "RB6_48") (pintype "passive"))
      (node (ref "XS1") (pin "1") (pinfunction "1_1") (pintype "passive"))
    )
    (net (code "15") (name "/RES") (class "Default")
      (node (ref "DA2") (pin "5") (pinfunction "~{RESET}_5") (pintype "passive"))
      (node (ref "DD2") (pin "1") (pinfunction "RD3_1") (pintype "passive"))
    )
    (net (code "16") (name "/RXC") (class "Default")
      (node (ref "DD2") (pin "44") (pinfunction "RB15_44") (pintype "passive"))
    )
    (net (code "17") (name "/SA1") (class "Default")
      (node (ref "DD2") (pin "54") (pinfunction "RD6_54") (pintype "passive"))
      (node (ref "XP1") (pin "7") (pinfunction "7_7") (pintype "passive"))
    )
    (net (code "18") (name "/SA2") (class "Default")
      (node (ref "DD2") (pin "55") (pinfunction "RC3_55") (pintype "passive"))
      (node (ref "XP1") (pin "10") (pinfunction "10_10") (pintype "passive"))
    )
    (net (code "19") (name "/SA3") (class "Default")
      (node (ref "DD2") (pin "60") (pinfunction "RB11_60") (pintype "passive"))
      (node (ref "XP1") (pin "8") (pinfunction "8_8") (pintype "passive"))
    )
    (net (code "20") (name "/SCL1") (class "Default")
      (node (ref "DA2") (pin "1") (pinfunction "SCLK_1") (pintype "passive"))
      (node (ref "DD2") (pin "4") (pinfunction "RC0_4") (pintype "passive"))
    )
    (net (code "21") (name "/SCL2") (class "Default")
      (node (ref "DD1") (pin "6") (pinfunction "SCK_6") (pintype "passive"))
      (node (ref "DD2") (pin "27") (pinfunction "RC1_27") (pintype "passive"))
    )
    (net (code "22") (name "/SDI1") (class "Default")
      (node (ref "DA2") (pin "13") (pinfunction "DOUT_13") (pintype "passive"))
      (node (ref "DD2") (pin "5") (pinfunction "RC13_5") (pintype "passive"))
    )
    (net (code "23") (name "/SDI2") (class "Default")
      (node (ref "DD1") (pin "2") (pinfunction "SO_2") (pintype "passive"))
      (node (ref "DD2") (pin "17") (pinfunction "RB9_17") (pintype "passive"))
    )
    (net (code "24") (name "/SDO1") (class "Default")
      (node (ref "DA2") (pin "14") (pinfunction "DIN_14") (pintype "passive"))
      (node (ref "DD2") (pin "11") (pinfunction "RC11_11") (pintype "passive"))
    )
    (net (code "25") (name "/SDO2") (class "Default")
      (node (ref "DD1") (pin "5") (pinfunction "SI_5") (pintype "passive"))
      (node (ref "DD2") (pin "18") (pinfunction "RB10_18") (pintype "passive"))
    )
    (net (code "26") (name "/TXC") (class "Default")
      (node (ref "DD2") (pin "37") (pinfunction "RC8_37") (pintype "passive"))
    )
    (net (code "27") (name "/V0") (class "Default")
      (node (ref "C29") (pin "1") (pinfunction "1_1") (pintype "passive"))
      (node (ref "DA3") (pin "6") (pinfunction "6_6") (pintype "passive"))
      (node (ref "DA3") (pin "7") (pinfunction "7_7") (pintype "passive"))
      (node (ref "DD2") (pin "12") (pinfunction "RC12_12") (pintype "passive"))
      (node (ref "DD2") (pin "23") (pinfunction "RC9_23") (pintype "passive"))
      (node (ref "R15") (pin "1") (pinfunction "1_1") (pintype "passive"))
      (node (ref "X10") (pin "1") (pinfunction "Contact0_1") (pintype "passive"))
      (node (ref "X7") (pin "1") (pintype "passive"))
    )
    (net (code "28") (name "/VPP") (class "Default")
      (node (ref "DD2") (pin "7") (pinfunction "~{Mclr}_7") (pintype "passive"))
      (node (ref "R3") (pin "2") (pinfunction "2_2") (pintype "passive"))
      (node (ref "XS1") (pin "5") (pinfunction "5_5") (pintype "passive"))
    )
    (net (code "29") (name "/WRID") (class "Default")
      (node (ref "DD2") (pin "61") (pinfunction "RB12_61") (pintype "passive"))
      (node (ref "VT3") (pin "2") (pinfunction "2_2") (pintype "passive"))
    )
    (net (code "30") (name "GND") (class "Default")
      (node (ref "C1") (pin "2") (pinfunction "2_2") (pintype "passive"))
      (node (ref "C10") (pin "2") (pinfunction "2_2") (pintype "passive"))
      (node (ref "C11") (pin "2") (pinfunction "2_2") (pintype "passive"))
      (node (ref "C12") (pin "2") (pinfunction "2_2") (pintype "passive"))
      (node (ref "C15") (pin "2") (pinfunction "2_2") (pintype "passive"))
      (node (ref "C16") (pin "2") (pinfunction "2_2") (pintype "passive"))
      (node (ref "C17") (pin "2") (pinfunction "2_2") (pintype "passive"))
      (node (ref "C18") (pin "1") (pinfunction "1_1") (pintype "passive"))
      (node (ref "C19") (pin "2") (pinfunction "2_2") (pintype "passive"))
      (node (ref "C2") (pin "2") (pinfunction "2_2") (pintype "passive"))
      (node (ref "C20") (pin "2") (pinfunction "2_2") (pintype "passive"))
      (node (ref "C21") (pin "2") (pinfunction "2_2") (pintype "passive"))
      (node (ref "C22") (pin "2") (pinfunction "2_2") (pintype "passive"))
      (node (ref "C24") (pin "1") (pinfunction "1_1") (pintype "passive"))
      (node (ref "C26") (pin "2") (pinfunction "2_2") (pintype "passive"))
      (node (ref "C27") (pin "2") (pinfunction "2_2") (pintype "passive"))
      (node (ref "C28") (pin "2") (pinfunction "2_2") (pintype "passive"))
      (node (ref "C29") (pin "2") (pinfunction "2_2") (pintype "passive"))
      (node (ref "C3") (pin "2") (pinfunction "2_2") (pintype "passive"))
      (node (ref "C30") (pin "2") (pinfunction "2_2") (pintype "passive"))
      (node (ref "C31") (pin "2") (pinfunction "2_2") (pintype "passive"))
      (node (ref "C35") (pin "2") (pinfunction "2_2") (pintype "passive"))
      (node (ref "C39") (pin "2") (pinfunction "2_2") (pintype "passive"))
      (node (ref "C4") (pin "2") (pinfunction "2_2") (pintype "passive"))
      (node (ref "C40") (pin "2") (pinfunction "2_2") (pintype "passive"))
      (node (ref "C5") (pin "2") (pinfunction "2_2") (pintype "passive"))
      (node (ref "C6") (pin "1") (pinfunction "1_1") (pintype "passive"))
      (node (ref "C7") (pin "2") (pinfunction "2_2") (pintype "passive"))
      (node (ref "C8") (pin "2") (pinfunction "2_2") (pintype "passive"))
      (node (ref "C9") (pin "2") (pinfunction "2_2") (pintype "passive"))
      (node (ref "DA1") (pin "2") (pinfunction "GND_2") (pintype "passive"))
      (node (ref "DA2") (pin "10") (pinfunction "REF_IN-_10") (pintype "passive"))
      (node (ref "DA2") (pin "16") (pinfunction "GND_16") (pintype "power_in"))
      (node (ref "DA3") (pin "4") (pinfunction "4_4") (pintype "passive"))
      (node (ref "DA4") (pin "2") (pinfunction "GND_2") (pintype "passive"))
      (node (ref "DA5") (pin "4") (pinfunction "4_4") (pintype "passive"))
      (node (ref "DD1") (pin "4") (pinfunction "Vss_4") (pintype "passive"))
      (node (ref "DD2") (pin "20") (pinfunction "AVss_20") (pintype "passive"))
      (node (ref "DD2") (pin "25") (pinfunction "Vss_25") (pintype "passive"))
      (node (ref "DD2") (pin "41") (pinfunction "Vss_41") (pintype "passive"))
      (node (ref "DD2") (pin "9") (pinfunction "Vss_9") (pintype "passive"))
      (node (ref "R13") (pin "2") (pinfunction "2_2") (pintype "passive"))
      (node (ref "R14") (pin "2") (pinfunction "2_2") (pintype "passive"))
      (node (ref "R20") (pin "1") (pinfunction "1_1") (pintype "passive"))
      (node (ref "R23") (pin "1") (pinfunction "1_1") (pintype "passive"))
      (node (ref "R7") (pin "1") (pinfunction "1_1") (pintype "passive"))
      (node (ref "VD1") (pin "1") (pinfunction "A_1") (pintype "passive"))
      (node (ref "VD2") (pin "1") (pinfunction "A_1") (pintype "passive"))
      (node (ref "VD3") (pin "1") (pinfunction "A_1") (pintype "passive"))
      (node (ref "X3") (pin "1") (pintype "passive"))
      (node (ref "XP1") (pin "11") (pinfunction "11_11") (pintype "passive"))
      (node (ref "XP1") (pin "14") (pinfunction "14_14") (pintype "passive"))
      (node (ref "XS1") (pin "4") (pinfunction "4_4") (pintype "passive"))
    )
    (net (code "31") (name "Net-(C4-Pad1)") (class "Default")
      (node (ref "C4") (pin "1") (pinfunction "1_1") (pintype "passive"))
      (node (ref "R2") (pin "2") (pinfunction "2_2") (pintype "passive"))
      (node (ref "R3") (pin "1") (pinfunction "1_1") (pintype "passive"))
    )
    (net (code "32") (name "Net-(C24-Pad2)") (class "Default")
      (node (ref "C24") (pin "2") (pinfunction "2_2") (pintype "passive"))
      (node (ref "DA3") (pin "3") (pinfunction "3_3") (pintype "passive"))
      (node (ref "R18") (pin "1") (pinfunction "1_1") (pintype "passive"))
    )
    (net (code "33") (name "Net-(C25-Pad2)") (class "Default")
      (node (ref "C25") (pin "2") (pinfunction "2_2") (pintype "passive"))
      (node (ref "C26") (pin "1") (pinfunction "1_1") (pintype "passive"))
      (node (ref "DA3") (pin "5") (pinfunction "5_5") (pintype "passive"))
      (node (ref "R19") (pin "2") (pinfunction "2_2") (pintype "passive"))
      (node (ref "R20") (pin "2") (pinfunction "2_2") (pintype "passive"))
    )
    (net (code "34") (name "Net-(DA2-AIN1+)") (class "Default")
      (node (ref "C10") (pin "1") (pinfunction "1_1") (pintype "passive"))
      (node (ref "C13") (pin "1") (pinfunction "1_1") (pintype "passive"))
      (node (ref "C14") (pin "1") (pinfunction "1_1") (pintype "passive"))
      (node (ref "DA2") (pin "6") (pinfunction "AIN2+_6") (pintype "passive"))
      (node (ref "DA2") (pin "7") (pinfunction "AIN1+_7") (pintype "passive"))
      (node (ref "R8") (pin "2") (pinfunction "2_2") (pintype "passive"))
    )
    (net (code "35") (name "Net-(DA2-AIN1-)") (class "Default")
      (node (ref "C12") (pin "1") (pinfunction "1_1") (pintype "passive"))
      (node (ref "C13") (pin "2") (pinfunction "2_2") (pintype "passive"))
      (node (ref "DA2") (pin "8") (pinfunction "AIN1-_8") (pintype "passive"))
      (node (ref "R9") (pin "2") (pinfunction "2_2") (pintype "passive"))
    )
    (net (code "36") (name "Net-(DA2-AIN2-)") (class "Default")
      (node (ref "C14") (pin "2") (pinfunction "2_2") (pintype "passive"))
      (node (ref "C15") (pin "1") (pinfunction "1_1") (pintype "passive"))
      (node (ref "DA2") (pin "11") (pinfunction "AIN2-_11") (pintype "passive"))
      (node (ref "DA2") (pin "9") (pinfunction "REF_IN+_9") (pintype "passive"))
      (node (ref "R10") (pin "2") (pinfunction "2_2") (pintype "passive"))
    )
    (net (code "37") (name "Net-(DA4-BST)") (class "Default")
      (node (ref "C23") (pin "2") (pinfunction "2_2") (pintype "passive"))
      (node (ref "DA4") (pin "1") (pinfunction "BST_1") (pintype "passive"))
    )
    (net (code "38") (name "Net-(DA4-EN)") (class "Default")
      (node (ref "DA4") (pin "4") (pinfunction "EN_4") (pintype "passive"))
      (node (ref "R21") (pin "2") (pinfunction "2_2") (pintype "passive"))
      (node (ref "VD2") (pin "2") (pinfunction "K_2") (pintype "passive"))
    )
    (net (code "39") (name "Net-(DA4-FB)") (class "Default")
      (node (ref "DA4") (pin "3") (pinfunction "FB_3") (pintype "passive"))
      (node (ref "R12") (pin "2") (pinfunction "2_2") (pintype "passive"))
      (node (ref "R13") (pin "1") (pinfunction "1_1") (pintype "passive"))
      (node (ref "R14") (pin "1") (pinfunction "1_1") (pintype "passive"))
    )
    (net (code "40") (name "Net-(DA4-SW)") (class "Default")
      (node (ref "C23") (pin "1") (pinfunction "1_1") (pintype "passive"))
      (node (ref "DA4") (pin "6") (pinfunction "SW_6") (pintype "passive"))
      (node (ref "L2") (pin "2") (pinfunction "2_2") (pintype "passive"))
      (node (ref "VD1") (pin "2") (pinfunction "K_2") (pintype "passive"))
    )
    (net (code "41") (name "Net-(DA4-Vin)") (class "Default")
      (node (ref "C27") (pin "1") (pinfunction "1_1") (pintype "passive"))
      (node (ref "DA4") (pin "5") (pinfunction "Vin_5") (pintype "passive"))
      (node (ref "R22") (pin "1") (pinfunction "1_1") (pintype "passive"))
      (node (ref "VD3") (pin "2") (pinfunction "K_2") (pintype "passive"))
    )
    (net (code "42") (name "Net-(DA5-Pad3)") (class "Default")
      (node (ref "DA5") (pin "3") (pinfunction "3_3") (pintype "passive"))
      (node (ref "R17") (pin "2") (pinfunction "2_2") (pintype "passive"))
    )
    (net (code "43") (name "Net-(DA5-Pad5)") (class "Default")
      (node (ref "DA5") (pin "5") (pinfunction "5_5") (pintype "passive"))
      (node (ref "R16") (pin "2") (pinfunction "2_2") (pintype "passive"))
    )
    (net (code "44") (name "Net-(DD2-AVdd)") (class "Default")
      (node (ref "C16") (pin "1") (pinfunction "1_1") (pintype "passive"))
      (node (ref "DD2") (pin "19") (pinfunction "AVdd_19") (pintype "passive"))
      (node (ref "L1") (pin "2") (pinfunction "2_2") (pintype "passive"))
    )
    (net (code "45") (name "Net-(DD2-Vcap)") (class "Default")
      (node (ref "C19") (pin "1") (pinfunction "1_1") (pintype "passive"))
      (node (ref "DD2") (pin "56") (pinfunction "Vcap_56") (pintype "passive"))
    )
    (net (code "46") (name "Net-(R4-Pad1)") (class "Default")
      (node (ref "R4") (pin "1") (pinfunction "1_1") (pintype "passive"))
      (node (ref "VT1") (pin "3") (pinfunction "3_3") (pintype "passive"))
      (node (ref "VT1") (pin "6") (pinfunction "6_6") (pintype "passive"))
      (node (ref "XP1") (pin "1") (pinfunction "1_1") (pintype "passive"))
    )
    (net (code "47") (name "Net-(R5-Pad1)") (class "Default")
      (node (ref "R5") (pin "1") (pinfunction "1_1") (pintype "passive"))
      (node (ref "VT2") (pin "3") (pinfunction "3_3") (pintype "passive"))
      (node (ref "VT2") (pin "6") (pinfunction "6_6") (pintype "passive"))
      (node (ref "XP1") (pin "5") (pinfunction "5_5") (pintype "passive"))
    )
    (net (code "48") (name "Net-(R6-Pad1)") (class "Default")
      (node (ref "R6") (pin "1") (pinfunction "1_1") (pintype "passive"))
      (node (ref "VT3") (pin "3") (pinfunction "3_3") (pintype "passive"))
      (node (ref "VT3") (pin "6") (pinfunction "6_6") (pintype "passive"))
      (node (ref "XP1") (pin "6") (pinfunction "6_6") (pintype "passive"))
    )
    (net (code "49") (name "Net-(R10-Pad1)") (class "Default")
      (node (ref "R10") (pin "1") (pinfunction "1_1") (pintype "passive"))
      (node (ref "R7") (pin "2") (pinfunction "2_2") (pintype "passive"))
      (node (ref "R9") (pin "1") (pinfunction "1_1") (pintype "passive"))
      (node (ref "X2") (pin "1") (pintype "passive"))
    )
    (net (code "50") (name "Net-(R11-Pad1)") (class "Default")
      (node (ref "R11") (pin "1") (pinfunction "1_1") (pintype "passive"))
      (node (ref "R8") (pin "1") (pinfunction "1_1") (pintype "passive"))
      (node (ref "X1") (pin "1") (pintype "passive"))
    )
    (net (code "51") (name "Net-(R21-Pad1)") (class "Default")
      (node (ref "R21") (pin "1") (pinfunction "1_1") (pintype "passive"))
      (node (ref "R22") (pin "2") (pinfunction "2_2") (pintype "passive"))
      (node (ref "X13") (pin "1") (pintype "passive"))
    )
    (net (code "52") (name "Net-(R23-Pad2)") (class "Default")
      (node (ref "R23") (pin "2") (pinfunction "2_2") (pintype "passive"))
      (node (ref "X14") (pin "1") (pintype "passive"))
    )
    (net (code "53") (name "Net-(X4-Contact0)") (class "Default")
      (node (ref "DA3") (pin "1") (pinfunction "1_1") (pintype "passive"))
      (node (ref "DA3") (pin "2") (pinfunction "2_2") (pintype "passive"))
      (node (ref "R17") (pin "1") (pinfunction "1_1") (pintype "passive"))
      (node (ref "X4") (pin "1") (pinfunction "Contact0_1") (pintype "passive"))
      (node (ref "X5") (pin "1") (pintype "passive"))
    )
    (net (code "54") (name "Net-(X8-Contact0)") (class "Default")
      (node (ref "R15") (pin "2") (pinfunction "2_2") (pintype "passive"))
      (node (ref "R16") (pin "1") (pinfunction "1_1") (pintype "passive"))
      (node (ref "X6") (pin "1") (pintype "passive"))
      (node (ref "X8") (pin "1") (pinfunction "Contact0_1") (pintype "passive"))
    )
    (net (code "55") (name "Net-(ZQ1-OSC1)") (class "Default")
      (node (ref "C3") (pin "1") (pinfunction "1_1") (pintype "passive"))
      (node (ref "R1") (pin "2") (pinfunction "2_2") (pintype "passive"))
      (node (ref "ZQ1") (pin "1") (pinfunction "OSC1_1") (pintype "passive"))
    )
    (net (code "56") (name "unconnected-(DA1-NC-Pad4)") (class "Default")
      (node (ref "DA1") (pin "4") (pinfunction "NC_4") (pintype "passive+no_connect"))
    )
    (net (code "57") (name "unconnected-(DA1-Pad4)") (class "Default")
      (node (ref "DA1") (pin "4") (pintype "passive"))
    )
    (net (code "58") (name "unconnected-(DA2-MCLK_OUT-Pad3)") (class "Default")
      (node (ref "DA2") (pin "3") (pinfunction "MCLK_OUT_3") (pintype "passive+no_connect"))
    )
    (net (code "59") (name "unconnected-(DD2-RA0-Pad13)") (class "Default")
      (node (ref "DD2") (pin "13") (pinfunction "RA0_13") (pintype "passive+no_connect"))
    )
    (net (code "60") (name "unconnected-(DD2-RB4-Pad33)") (class "Default")
      (node (ref "DD2") (pin "33") (pinfunction "RB4_33") (pintype "passive+no_connect"))
    )
    (net (code "61") (name "unconnected-(DD2-RB5-Pad46)") (class "Default")
      (node (ref "DD2") (pin "46") (pinfunction "RB5_46") (pintype "passive+no_connect"))
    )
    (net (code "62") (name "unconnected-(DD2-RB8-Pad43)") (class "Default")
      (node (ref "DD2") (pin "43") (pinfunction "RB8_43") (pintype "passive+no_connect"))
    )
    (net (code "63") (name "unconnected-(DD2-RC2-Pad35)") (class "Default")
      (node (ref "DD2") (pin "35") (pinfunction "RC2_35") (pintype "passive"))
    )
    (net (code "64") (name "unconnected-(DD2-RC4-Pad50)") (class "Default")
      (node (ref "DD2") (pin "50") (pinfunction "RC4_50") (pintype "passive+no_connect"))
    )
    (net (code "65") (name "unconnected-(DD2-RC5-Pad51)") (class "Default")
      (node (ref "DD2") (pin "51") (pinfunction "RC5_51") (pintype "passive+no_connect"))
    )
    (net (code "66") (name "unconnected-(DD2-RC6-Pad52)") (class "Default")
      (node (ref "DD2") (pin "52") (pinfunction "RC6_52") (pintype "passive+no_connect"))
    )
    (net (code "67") (name "unconnected-(DD2-RC7-Pad36)") (class "Default")
      (node (ref "DD2") (pin "36") (pinfunction "RC7_36") (pintype "passive+no_connect"))
    )
    (net (code "68") (name "unconnected-(DD2-RC10-Pad24)") (class "Default")
      (node (ref "DD2") (pin "24") (pinfunction "RC10_24") (pintype "passive+no_connect"))
    )
    (net (code "69") (name "unconnected-(DD2-RC14-Pad34)") (class "Default")
      (node (ref "DD2") (pin "34") (pinfunction "RC14_34") (pintype "passive+no_connect"))
    )
    (net (code "70") (name "unconnected-(DD2-RC15-Pad31)") (class "Default")
      (node (ref "DD2") (pin "31") (pinfunction "RC15_31") (pintype "passive+no_connect"))
    )
    (net (code "71") (name "unconnected-(DD2-RD0-Pad47)") (class "Default")
      (node (ref "DD2") (pin "47") (pinfunction "RD0_47") (pintype "passive+no_connect"))
    )
    (net (code "72") (name "unconnected-(DD2-RD1-Pad64)") (class "Default")
      (node (ref "DD2") (pin "64") (pinfunction "RD1_64") (pintype "passive+no_connect"))
    )
    (net (code "73") (name "unconnected-(DD2-RD2-Pad30)") (class "Default")
      (node (ref "DD2") (pin "30") (pinfunction "RD2_30") (pintype "passive+no_connect"))
    )
    (net (code "74") (name "unconnected-(DD2-RD4-Pad58)") (class "Default")
      (node (ref "DD2") (pin "58") (pinfunction "RD4_58") (pintype "passive+no_connect"))
    )
    (net (code "75") (name "unconnected-(DD2-RD5-Pad53)") (class "Default")
      (node (ref "DD2") (pin "53") (pinfunction "RD5_53") (pintype "passive+no_connect"))
    )
    (net (code "76") (name "unconnected-(DD2-RD7-Pad21)") (class "Default")
      (node (ref "DD2") (pin "21") (pinfunction "RD7_21") (pintype "passive+no_connect"))
    )
    (net (code "77") (name "unconnected-(DD2-RD8-Pad42)") (class "Default")
      (node (ref "DD2") (pin "42") (pinfunction "RD8_42") (pintype "passive+no_connect"))
    )
    (net (code "78") (name "unconnected-(DD2-RD9-Pad40)") (class "Default")
      (node (ref "DD2") (pin "40") (pinfunction "RD9_40") (pintype "passive+no_connect"))
    )
    (net (code "79") (name "unconnected-(DD2-RD10-Pad6)") (class "Default")
      (node (ref "DD2") (pin "6") (pinfunction "RD10_6") (pintype "passive+no_connect"))
    )
    (net (code "80") (name "unconnected-(DD2-RD11-Pad45)") (class "Default")
      (node (ref "DD2") (pin "45") (pinfunction "RD11_45") (pintype "passive+no_connect"))
    )
    (net (code "81") (name "unconnected-(DD2-RD12-Pad8)") (class "Default")
      (node (ref "DD2") (pin "8") (pinfunction "RD12_8") (pintype "passive+no_connect"))
    )
    (net (code "82") (name "unconnected-(DD2-RD13-Pad22)") (class "Default")
      (node (ref "DD2") (pin "22") (pinfunction "RD13_22") (pintype "passive+no_connect"))
    )
    (net (code "83") (name "unconnected-(DD2-RD14-Pad39)") (class "Default")
      (node (ref "DD2") (pin "39") (pinfunction "RD14_39") (pintype "passive+no_connect"))
    )
    (net (code "84") (name "unconnected-(DD2-RD15-Pad59)") (class "Default")
      (node (ref "DD2") (pin "59") (pinfunction "RD15_59") (pintype "passive+no_connect"))
    )
    (net (code "85") (name "unconnected-(XP1-Pad2)") (class "Default")
      (node (ref "XP1") (pin "2") (pinfunction "2_2") (pintype "passive+no_connect"))
    )
    (net (code "86") (name "unconnected-(XP1-Pad4)") (class "Default")
      (node (ref "XP1") (pin "4") (pinfunction "4_4") (pintype "passive+no_connect"))
    )
    (net (code "87") (name "unconnected-(XP1-Pad9)") (class "Default")
      (node (ref "XP1") (pin "9") (pinfunction "9_9") (pintype "passive+no_connect"))
    )
    (net (code "88") (name "unconnected-(XP1-Pad13)") (class "Default")
      (node (ref "XP1") (pin "13") (pinfunction "13_13") (pintype "passive+no_connect"))
    )
  )
)
